# IG01.net
KiCad netlist of a schematic drawn in EAGLE
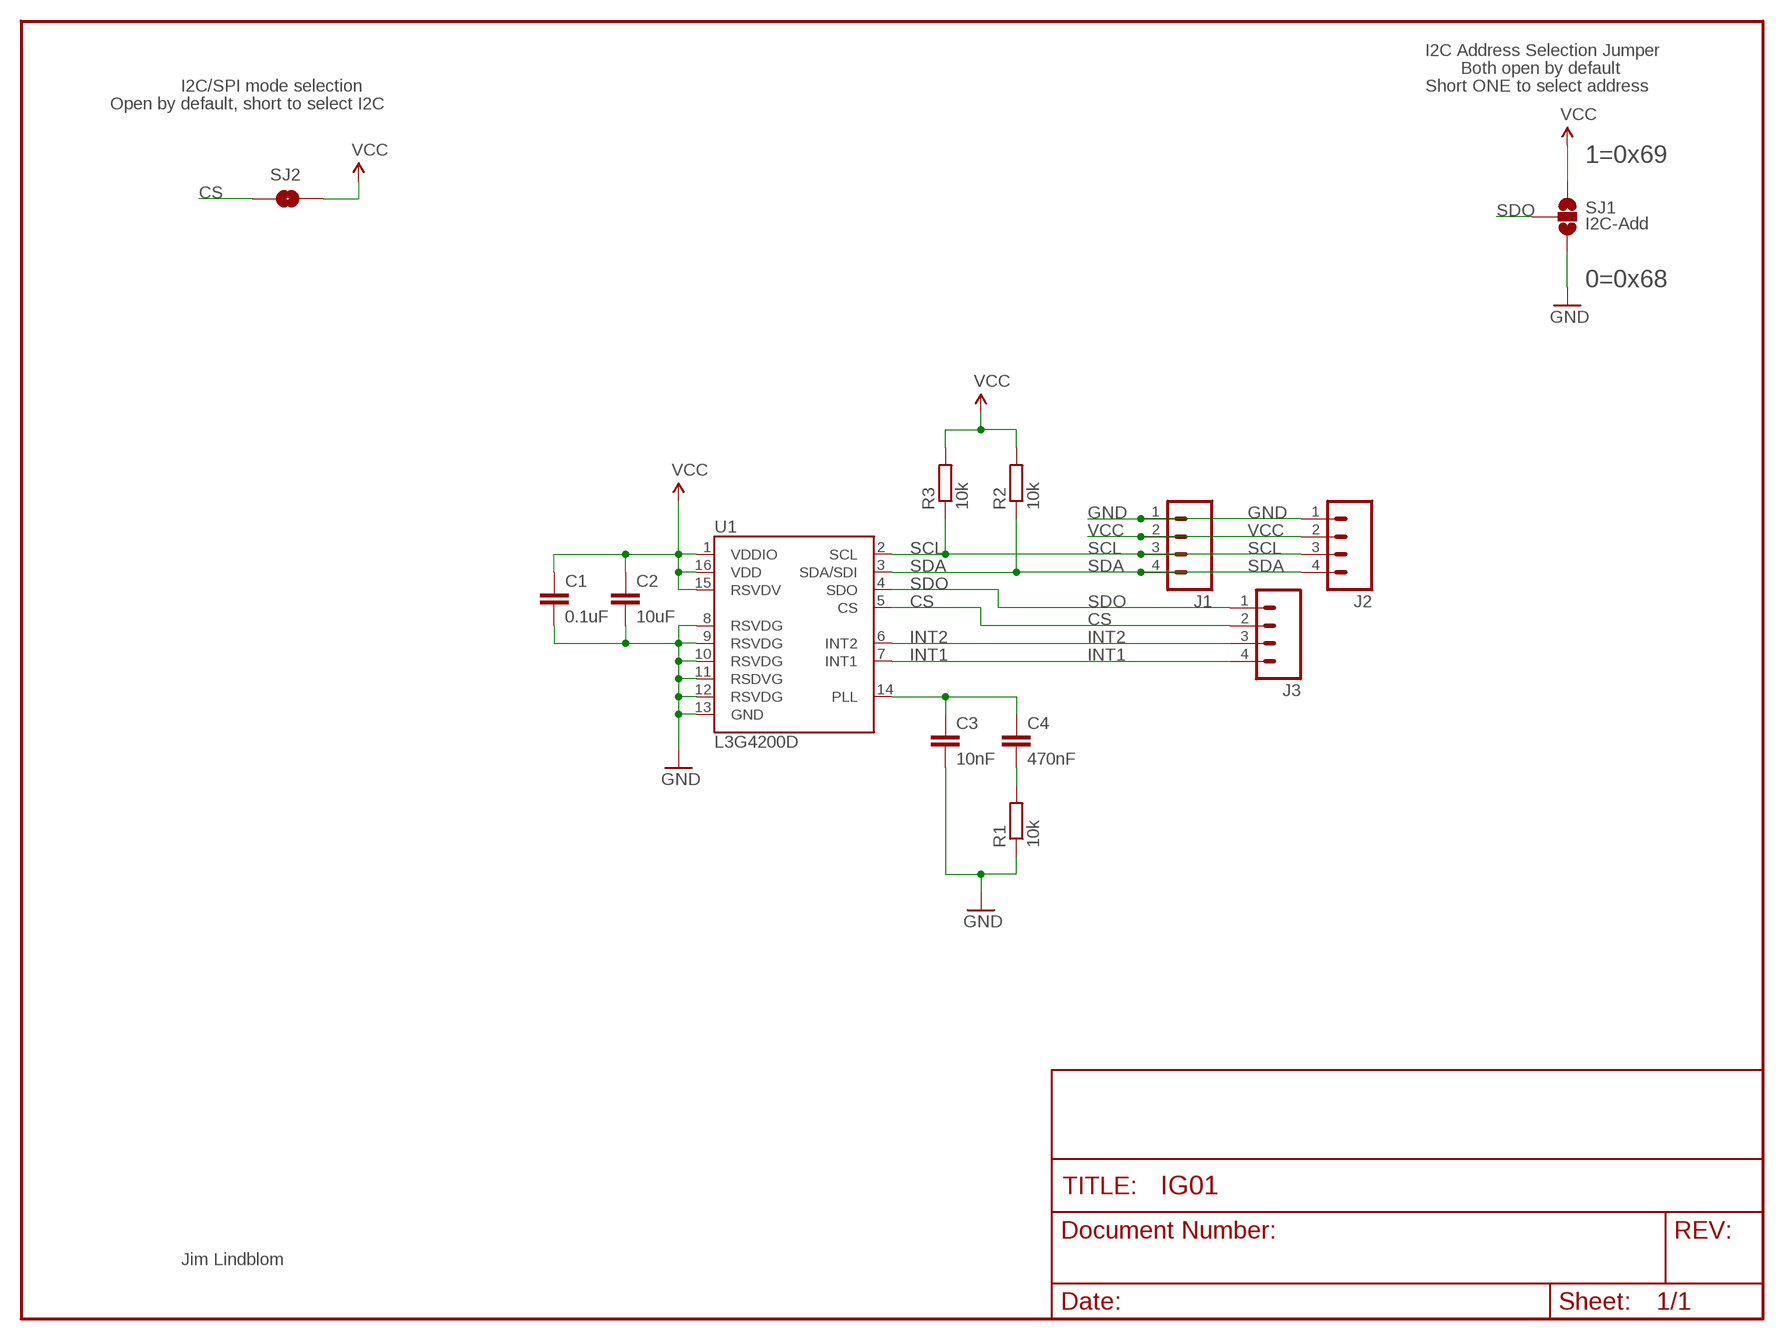
[diagram p0: schematic, sheet 1]

(export (version "E")
  (design (tool "Eeschema 10.0.6"))
  (components
    (comp (ref "C1")
      (value "0.1uF")
      (footprint "eagle-import:C0805")
      (libsource (lib "eagle-import") (part "C-EUC0805"))
    )
    (comp (ref "C2")
      (value "10uF")
      (footprint "eagle-import:C1206")
      (libsource (lib "eagle-import") (part "C-EUC1206"))
    )
    (comp (ref "C3")
      (value "10nF")
      (footprint "eagle-import:C0805")
      (libsource (lib "eagle-import") (part "C-EUC0805"))
    )
    (comp (ref "C4")
      (value "470nF")
      (footprint "eagle-import:C0805")
      (libsource (lib "eagle-import") (part "C-EUC0805"))
    )
    (comp (ref "J1")
      (value "M04PTH")
      (footprint "eagle-import:1X04")
      (libsource (lib "eagle-import") (part "M04PTH"))
    )
    (comp (ref "J2")
      (value "M04PTH")
      (footprint "eagle-import:1X04")
      (libsource (lib "eagle-import") (part "M04PTH"))
    )
    (comp (ref "J3")
      (value "M04PTH")
      (footprint "eagle-import:1X04")
      (libsource (lib "eagle-import") (part "M04PTH"))
    )
    (comp (ref "R1")
      (value "10k")
      (footprint "eagle-import:M0805")
      (libsource (lib "eagle-import") (part "R-EU_M0805"))
    )
    (comp (ref "R2")
      (value "10k")
      (footprint "eagle-import:M0805")
      (libsource (lib "eagle-import") (part "R-EU_M0805"))
    )
    (comp (ref "R3")
      (value "10k")
      (footprint "eagle-import:M0805")
      (libsource (lib "eagle-import") (part "R-EU_M0805"))
    )
    (comp (ref "SJ1")
      (value "I2C-Add")
      (footprint "eagle-import:SJ_3")
      (libsource (lib "eagle-import") (part "SOLDERJUMPER_2WAYS"))
    )
    (comp (ref "SJ2")
      (value "I2C-Mode")
      (footprint "eagle-import:SJ_2S-NO")
      (libsource (lib "eagle-import") (part "SOLDERJUMPERNO"))
    )
    (comp (ref "U1")
      (value "L3G4200D")
      (footprint "eagle-import:LGA16-4X4")
      (libsource (lib "eagle-import") (part "L3G4200D"))
    )
  )
  (nets
    (net (code "1") (name "/CS") (class "Default")
      (node (ref "J3") (pin "2") (pinfunction "2_2") (pintype "passive"))
      (node (ref "SJ2") (pin "1") (pinfunction "1_1") (pintype "passive"))
      (node (ref "U1") (pin "5") (pinfunction "CS_5") (pintype "bidirectional"))
    )
    (net (code "2") (name "/INT1") (class "Default")
      (node (ref "J3") (pin "4") (pinfunction "4_4") (pintype "passive"))
      (node (ref "U1") (pin "7") (pinfunction "INT1_7") (pintype "bidirectional"))
    )
    (net (code "3") (name "/INT2") (class "Default")
      (node (ref "J3") (pin "3") (pinfunction "3_3") (pintype "passive"))
      (node (ref "U1") (pin "6") (pinfunction "INT2_6") (pintype "bidirectional"))
    )
    (net (code "4") (name "/SCL") (class "Default")
      (node (ref "J1") (pin "3") (pinfunction "3_3") (pintype "passive"))
      (node (ref "J2") (pin "3") (pinfunction "3_3") (pintype "passive"))
      (node (ref "R3") (pin "1") (pinfunction "1_1") (pintype "passive"))
      (node (ref "U1") (pin "2") (pinfunction "SCL_2") (pintype "bidirectional"))
    )
    (net (code "5") (name "/SDA") (class "Default")
      (node (ref "J1") (pin "4") (pinfunction "4_4") (pintype "passive"))
      (node (ref "J2") (pin "4") (pinfunction "4_4") (pintype "passive"))
      (node (ref "R2") (pin "1") (pinfunction "1_1") (pintype "passive"))
      (node (ref "U1") (pin "3") (pinfunction "SDA/SDI_3") (pintype "bidirectional"))
    )
    (net (code "6") (name "/SDO") (class "Default")
      (node (ref "J3") (pin "1") (pinfunction "1_1") (pintype "passive"))
      (node (ref "SJ1") (pin "2") (pinfunction "2_2") (pintype "passive"))
      (node (ref "U1") (pin "4") (pinfunction "SDO_4") (pintype "bidirectional"))
    )
    (net (code "7") (name "GND") (class "Default")
      (node (ref "C1") (pin "2") (pinfunction "2_2") (pintype "passive"))
      (node (ref "C2") (pin "2") (pinfunction "2_2") (pintype "passive"))
      (node (ref "C3") (pin "2") (pinfunction "2_2") (pintype "passive"))
      (node (ref "J1") (pin "1") (pinfunction "1_1") (pintype "passive"))
      (node (ref "J2") (pin "1") (pinfunction "1_1") (pintype "passive"))
      (node (ref "R1") (pin "1") (pinfunction "1_1") (pintype "passive"))
      (node (ref "SJ1") (pin "3") (pinfunction "3_3") (pintype "passive"))
      (node (ref "U1") (pin "10") (pinfunction "RSVDG_10") (pintype "bidirectional"))
      (node (ref "U1") (pin "11") (pinfunction "RSDVG_11") (pintype "bidirectional"))
      (node (ref "U1") (pin "12") (pinfunction "RSVDG_12") (pintype "bidirectional"))
      (node (ref "U1") (pin "13") (pinfunction "GND_13") (pintype "bidirectional"))
      (node (ref "U1") (pin "8") (pinfunction "RSVDG_8") (pintype "bidirectional"))
      (node (ref "U1") (pin "9") (pinfunction "RSVDG_9") (pintype "bidirectional"))
    )
    (net (code "8") (name "Net-(C4-Pad2)") (class "Default")
      (node (ref "C4") (pin "2") (pinfunction "2_2") (pintype "passive"))
      (node (ref "R1") (pin "2") (pinfunction "2_2") (pintype "passive"))
    )
    (net (code "9") (name "Net-(U1-PLL)") (class "Default")
      (node (ref "C3") (pin "1") (pinfunction "1_1") (pintype "passive"))
      (node (ref "C4") (pin "1") (pinfunction "1_1") (pintype "passive"))
      (node (ref "U1") (pin "14") (pinfunction "PLL_14") (pintype "bidirectional"))
    )
    (net (code "10") (name "VCC") (class "Default")
      (node (ref "C1") (pin "1") (pinfunction "1_1") (pintype "passive"))
      (node (ref "C2") (pin "1") (pinfunction "1_1") (pintype "passive"))
      (node (ref "J1") (pin "2") (pinfunction "2_2") (pintype "passive"))
      (node (ref "J2") (pin "2") (pinfunction "2_2") (pintype "passive"))
      (node (ref "R2") (pin "2") (pinfunction "2_2") (pintype "passive"))
      (node (ref "R3") (pin "2") (pinfunction "2_2") (pintype "passive"))
      (node (ref "SJ1") (pin "1") (pinfunction "1_1") (pintype "passive"))
      (node (ref "SJ2") (pin "2") (pinfunction "2_2") (pintype "passive"))
      (node (ref "U1") (pin "1") (pinfunction "VDDIO_1") (pintype "bidirectional"))
      (node (ref "U1") (pin "15") (pinfunction "RSVDV_15") (pintype "bidirectional"))
      (node (ref "U1") (pin "16") (pinfunction "VDD_16") (pintype "bidirectional"))
    )
  )
)
